# design.net
KiCad netlist of a schematic drawn in EasyEDA Pro
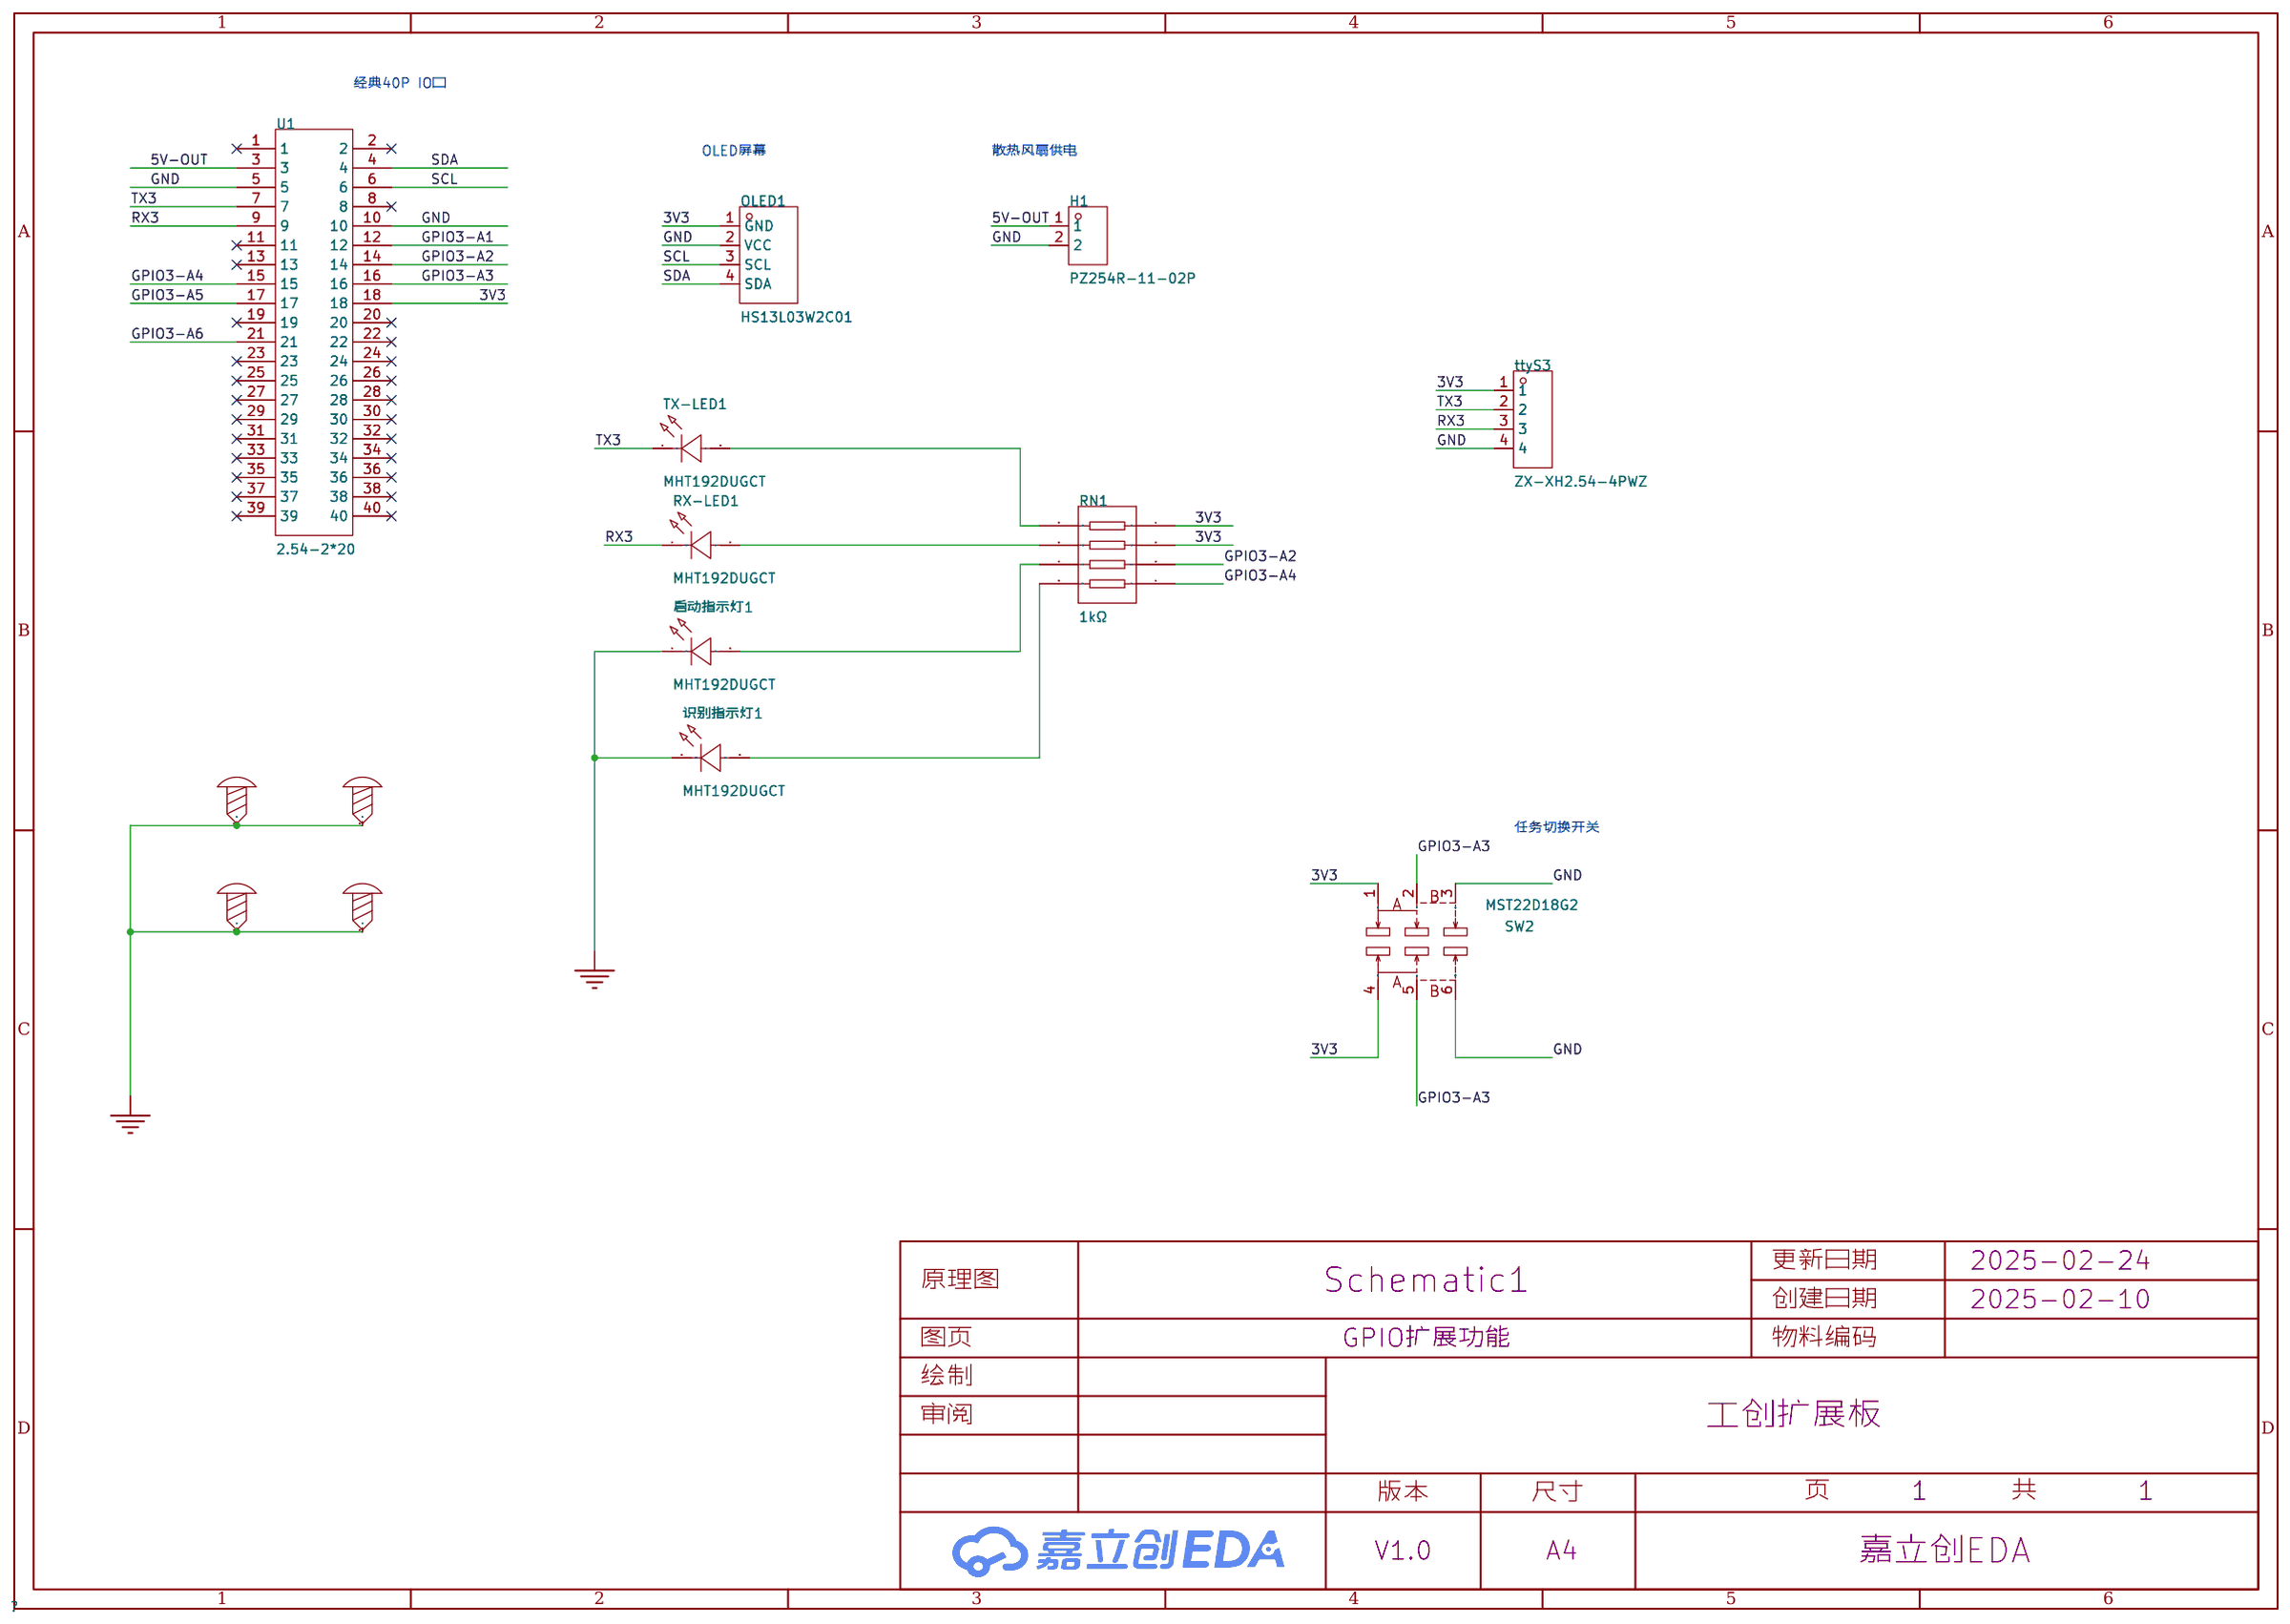
[diagram p0: schematic sheet]

(export (version "E")
  (design (tool "Eeschema 10.0.6"))
  (components
    (comp (ref "H1")
      (value "PZ254R-11-02P")
      (footprint "easyedapro:HDR-TH_2P-P2.54-H-M-W10.4")
      (fields (field (name "Manufacturer") "XFCN(兴飞)"))
      (libsource (lib "easyedapro") (part "PZ254R-11-02P"))
    )
    (comp (ref "OLED1")
      (value "HS13L03W2C01")
      (footprint "easyedapro:OLED-TH_L35.4-W33.5_HS13L03W2C01")
      (description "主控芯片:SH1106;接口类型:I2C;尺寸(inch):1.3;")
      (fields (field (name "Manufacturer") "HS(汉昇)"))
      (libsource (lib "easyedapro") (part "HS13L03W2C01"))
    )
    (comp (ref "RN1")
      (value "1kΩ")
      (footprint "easyedapro:RES-ARRAY-SMD_0603-8P-L3.2-W1.6-BL")
      (description "电阻器数:4;阻值:1kΩ;精度:±1%;单个元件功率:62.5mW;温度系数:±200ppm/°C;")
      (fields (field (name "Manufacturer Part") "YC164-FR-071KL") (field (name "Manufacturer") "YAGEO(国巨)"))
      (libsource (lib "easyedapro") (part "YC164-FR-071KL"))
    )
    (comp (ref "RX-LED1")
      (value "MHT192DUGCT")
      (footprint "easyedapro:LED0603-RD")
      (fields (field (name "Manufacturer") "MEIHUA(美华)"))
      (libsource (lib "easyedapro") (part "MHT192DUGCT"))
    )
    (comp (ref "SCREW1")
      (value "~")
      (footprint "easyedapro:M3螺丝")
      (libsource (lib "easyedapro") (part "螺丝孔"))
    )
    (comp (ref "SCREW2")
      (value "~")
      (footprint "easyedapro:M3螺丝")
      (libsource (lib "easyedapro") (part "螺丝孔"))
    )
    (comp (ref "SCREW3")
      (value "~")
      (footprint "easyedapro:M3螺丝")
      (libsource (lib "easyedapro") (part "螺丝孔"))
    )
    (comp (ref "SCREW4")
      (value "~")
      (footprint "easyedapro:M3螺丝")
      (libsource (lib "easyedapro") (part "螺丝孔"))
    )
    (comp (ref "SW2")
      (value "MST22D18G2")
      (footprint "easyedapro:SW-SMD_MST22D18G2")
      (description "电路结构:双刀双掷;安装方式:立贴;开关颜色:-;额定电流(DC):50mA;额定电压(DC):12V;额定电流(AC):-;额定电压(AC):-;机械寿命:1万次;")
      (fields (field (name "Manufacturer") "SHOU HAN(首韩)"))
      (libsource (lib "easyedapro") (part "MST22D18G2"))
    )
    (comp (ref "ttyS3")
      (value "ZX-XH2.54-4PWZ")
      (footprint "easyedapro:CONN-TH_4P-P2.50_ZX-XH2.54-4PWZ")
      (fields (field (name "Manufacturer") "Megastar(兆星)"))
      (libsource (lib "easyedapro") (part "ZX-XH2.54-4PWZ"))
    )
    (comp (ref "TX-LED1")
      (value "MHT192DUGCT")
      (footprint "easyedapro:LED0603-RD")
      (fields (field (name "Manufacturer") "MEIHUA(美华)"))
      (libsource (lib "easyedapro") (part "MHT192DUGCT"))
    )
    (comp (ref "U1")
      (value "2.54-2*20")
      (footprint "easyedapro:HDR-TH_40P-P2.54-V-F-R2-C20-S2.54")
      (fields (field (name "Manufacturer") "ZHOURI(洲日)"))
      (libsource (lib "easyedapro") (part "2.54-2*20"))
    )
    (comp (ref "启动指示灯1")
      (value "MHT192DUGCT")
      (footprint "easyedapro:LED0603-RD")
      (fields (field (name "Manufacturer") "MEIHUA(美华)"))
      (libsource (lib "easyedapro") (part "MHT192DUGCT"))
    )
    (comp (ref "识别指示灯1")
      (value "MHT192DUGCT")
      (footprint "easyedapro:LED0603-RD")
      (fields (field (name "Manufacturer") "MEIHUA(美华)"))
      (libsource (lib "easyedapro") (part "MHT192DUGCT"))
    )
  )
  (nets
    (net (code "1") (name "/3V3") (class "Default")
      (node (ref "OLED1") (pin "1") (pinfunction "GND_1") (pintype "unspecified"))
      (node (ref "RN1") (pin "3") (pinfunction "3_3") (pintype "input"))
      (node (ref "RN1") (pin "4") (pinfunction "4_4") (pintype "input"))
      (node (ref "SW2") (pin "1") (pinfunction "1_1") (pintype "unspecified"))
      (node (ref "SW2") (pin "4") (pinfunction "4_4") (pintype "unspecified"))
      (node (ref "U1") (pin "18") (pinfunction "18_18") (pintype "unspecified"))
      (node (ref "ttyS3") (pin "1") (pinfunction "1_1") (pintype "unspecified"))
    )
    (net (code "2") (name "/5V-OUT") (class "Default")
      (node (ref "H1") (pin "1") (pinfunction "1_1") (pintype "unspecified"))
      (node (ref "U1") (pin "3") (pinfunction "3_3") (pintype "unspecified"))
    )
    (net (code "3") (name "/GPIO3-A1") (class "Default")
      (node (ref "U1") (pin "12") (pinfunction "12_12") (pintype "unspecified"))
    )
    (net (code "4") (name "/GPIO3-A2") (class "Default")
      (node (ref "RN1") (pin "2") (pinfunction "2_2") (pintype "input"))
      (node (ref "U1") (pin "14") (pinfunction "14_14") (pintype "unspecified"))
    )
    (net (code "5") (name "/GPIO3-A3") (class "Default")
      (node (ref "SW2") (pin "2") (pinfunction "2_2") (pintype "unspecified"))
      (node (ref "SW2") (pin "5") (pinfunction "5_5") (pintype "unspecified"))
      (node (ref "U1") (pin "16") (pinfunction "16_16") (pintype "unspecified"))
    )
    (net (code "6") (name "/GPIO3-A4") (class "Default")
      (node (ref "RN1") (pin "1") (pinfunction "1_1") (pintype "input"))
      (node (ref "U1") (pin "15") (pinfunction "15_15") (pintype "unspecified"))
    )
    (net (code "7") (name "/GPIO3-A5") (class "Default")
      (node (ref "U1") (pin "17") (pinfunction "17_17") (pintype "unspecified"))
    )
    (net (code "8") (name "/GPIO3-A6") (class "Default")
      (node (ref "U1") (pin "21") (pinfunction "21_21") (pintype "unspecified"))
    )
    (net (code "9") (name "/RX3") (class "Default")
      (node (ref "RX-LED1") (pin "1") (pinfunction "K_1") (pintype "unspecified"))
      (node (ref "U1") (pin "9") (pinfunction "9_9") (pintype "unspecified"))
      (node (ref "ttyS3") (pin "3") (pinfunction "3_3") (pintype "unspecified"))
    )
    (net (code "10") (name "/SCL") (class "Default")
      (node (ref "OLED1") (pin "3") (pinfunction "SCL_3") (pintype "unspecified"))
      (node (ref "U1") (pin "6") (pinfunction "6_6") (pintype "unspecified"))
    )
    (net (code "11") (name "/SDA") (class "Default")
      (node (ref "OLED1") (pin "4") (pinfunction "SDA_4") (pintype "unspecified"))
      (node (ref "U1") (pin "4") (pinfunction "4_4") (pintype "unspecified"))
    )
    (net (code "12") (name "/TX3") (class "Default")
      (node (ref "TX-LED1") (pin "1") (pinfunction "K_1") (pintype "unspecified"))
      (node (ref "U1") (pin "7") (pinfunction "7_7") (pintype "unspecified"))
      (node (ref "ttyS3") (pin "2") (pinfunction "2_2") (pintype "unspecified"))
    )
    (net (code "13") (name "GND") (class "Default")
      (node (ref "H1") (pin "2") (pinfunction "2_2") (pintype "unspecified"))
      (node (ref "OLED1") (pin "2") (pinfunction "VCC_2") (pintype "unspecified"))
      (node (ref "SCREW1") (pin "1") (pinfunction "1_1") (pintype "input"))
      (node (ref "SCREW2") (pin "1") (pinfunction "1_1") (pintype "input"))
      (node (ref "SCREW3") (pin "1") (pinfunction "1_1") (pintype "input"))
      (node (ref "SCREW4") (pin "1") (pinfunction "1_1") (pintype "input"))
      (node (ref "SW2") (pin "3") (pinfunction "3_3") (pintype "unspecified"))
      (node (ref "SW2") (pin "6") (pinfunction "6_6") (pintype "unspecified"))
      (node (ref "U1") (pin "10") (pinfunction "10_10") (pintype "unspecified"))
      (node (ref "U1") (pin "5") (pinfunction "5_5") (pintype "unspecified"))
      (node (ref "ttyS3") (pin "4") (pinfunction "4_4") (pintype "unspecified"))
      (node (ref "启动指示灯1") (pin "1") (pinfunction "K_1") (pintype "unspecified"))
      (node (ref "识别指示灯1") (pin "1") (pinfunction "K_1") (pintype "unspecified"))
    )
    (net (code "14") (name "Net-(RX-LED1-A)") (class "Default")
      (node (ref "RN1") (pin "6") (pinfunction "6_6") (pintype "input"))
      (node (ref "RX-LED1") (pin "2") (pinfunction "A_2") (pintype "unspecified"))
    )
    (net (code "15") (name "Net-(TX-LED1-A)") (class "Default")
      (node (ref "RN1") (pin "5") (pinfunction "5_5") (pintype "input"))
      (node (ref "TX-LED1") (pin "2") (pinfunction "A_2") (pintype "unspecified"))
    )
    (net (code "16") (name "Net-(启动指示灯1-A)") (class "Default")
      (node (ref "RN1") (pin "7") (pinfunction "7_7") (pintype "input"))
      (node (ref "启动指示灯1") (pin "2") (pinfunction "A_2") (pintype "unspecified"))
    )
    (net (code "17") (name "Net-(识别指示灯1-A)") (class "Default")
      (node (ref "RN1") (pin "8") (pinfunction "8_8") (pintype "input"))
      (node (ref "识别指示灯1") (pin "2") (pinfunction "A_2") (pintype "unspecified"))
    )
    (net (code "18") (name "unconnected-(U1-Pad1)") (class "Default")
      (node (ref "U1") (pin "1") (pinfunction "1_1") (pintype "unspecified+no_connect"))
    )
    (net (code "19") (name "unconnected-(U1-Pad2)") (class "Default")
      (node (ref "U1") (pin "2") (pinfunction "2_2") (pintype "unspecified+no_connect"))
    )
    (net (code "20") (name "unconnected-(U1-Pad8)") (class "Default")
      (node (ref "U1") (pin "8") (pinfunction "8_8") (pintype "unspecified+no_connect"))
    )
    (net (code "21") (name "unconnected-(U1-Pad11)") (class "Default")
      (node (ref "U1") (pin "11") (pinfunction "11_11") (pintype "unspecified+no_connect"))
    )
    (net (code "22") (name "unconnected-(U1-Pad13)") (class "Default")
      (node (ref "U1") (pin "13") (pinfunction "13_13") (pintype "unspecified+no_connect"))
    )
    (net (code "23") (name "unconnected-(U1-Pad19)") (class "Default")
      (node (ref "U1") (pin "19") (pinfunction "19_19") (pintype "unspecified+no_connect"))
    )
    (net (code "24") (name "unconnected-(U1-Pad20)") (class "Default")
      (node (ref "U1") (pin "20") (pinfunction "20_20") (pintype "unspecified+no_connect"))
    )
    (net (code "25") (name "unconnected-(U1-Pad22)") (class "Default")
      (node (ref "U1") (pin "22") (pinfunction "22_22") (pintype "unspecified+no_connect"))
    )
    (net (code "26") (name "unconnected-(U1-Pad23)") (class "Default")
      (node (ref "U1") (pin "23") (pinfunction "23_23") (pintype "unspecified+no_connect"))
    )
    (net (code "27") (name "unconnected-(U1-Pad24)") (class "Default")
      (node (ref "U1") (pin "24") (pinfunction "24_24") (pintype "unspecified+no_connect"))
    )
    (net (code "28") (name "unconnected-(U1-Pad25)") (class "Default")
      (node (ref "U1") (pin "25") (pinfunction "25_25") (pintype "unspecified+no_connect"))
    )
    (net (code "29") (name "unconnected-(U1-Pad26)") (class "Default")
      (node (ref "U1") (pin "26") (pinfunction "26_26") (pintype "unspecified+no_connect"))
    )
    (net (code "30") (name "unconnected-(U1-Pad27)") (class "Default")
      (node (ref "U1") (pin "27") (pinfunction "27_27") (pintype "unspecified+no_connect"))
    )
    (net (code "31") (name "unconnected-(U1-Pad28)") (class "Default")
      (node (ref "U1") (pin "28") (pinfunction "28_28") (pintype "unspecified+no_connect"))
    )
    (net (code "32") (name "unconnected-(U1-Pad29)") (class "Default")
      (node (ref "U1") (pin "29") (pinfunction "29_29") (pintype "unspecified+no_connect"))
    )
    (net (code "33") (name "unconnected-(U1-Pad30)") (class "Default")
      (node (ref "U1") (pin "30") (pinfunction "30_30") (pintype "unspecified+no_connect"))
    )
    (net (code "34") (name "unconnected-(U1-Pad31)") (class "Default")
      (node (ref "U1") (pin "31") (pinfunction "31_31") (pintype "unspecified+no_connect"))
    )
    (net (code "35") (name "unconnected-(U1-Pad32)") (class "Default")
      (node (ref "U1") (pin "32") (pinfunction "32_32") (pintype "unspecified+no_connect"))
    )
    (net (code "36") (name "unconnected-(U1-Pad33)") (class "Default")
      (node (ref "U1") (pin "33") (pinfunction "33_33") (pintype "unspecified+no_connect"))
    )
    (net (code "37") (name "unconnected-(U1-Pad34)") (class "Default")
      (node (ref "U1") (pin "34") (pinfunction "34_34") (pintype "unspecified+no_connect"))
    )
    (net (code "38") (name "unconnected-(U1-Pad35)") (class "Default")
      (node (ref "U1") (pin "35") (pinfunction "35_35") (pintype "unspecified+no_connect"))
    )
    (net (code "39") (name "unconnected-(U1-Pad36)") (class "Default")
      (node (ref "U1") (pin "36") (pinfunction "36_36") (pintype "unspecified+no_connect"))
    )
    (net (code "40") (name "unconnected-(U1-Pad37)") (class "Default")
      (node (ref "U1") (pin "37") (pinfunction "37_37") (pintype "unspecified+no_connect"))
    )
    (net (code "41") (name "unconnected-(U1-Pad38)") (class "Default")
      (node (ref "U1") (pin "38") (pinfunction "38_38") (pintype "unspecified+no_connect"))
    )
    (net (code "42") (name "unconnected-(U1-Pad39)") (class "Default")
      (node (ref "U1") (pin "39") (pinfunction "39_39") (pintype "unspecified+no_connect"))
    )
    (net (code "43") (name "unconnected-(U1-Pad40)") (class "Default")
      (node (ref "U1") (pin "40") (pinfunction "40_40") (pintype "unspecified+no_connect"))
    )
  )
)
